# sensor-6.net
KiCad netlist of a schematic drawn in Altium Designer
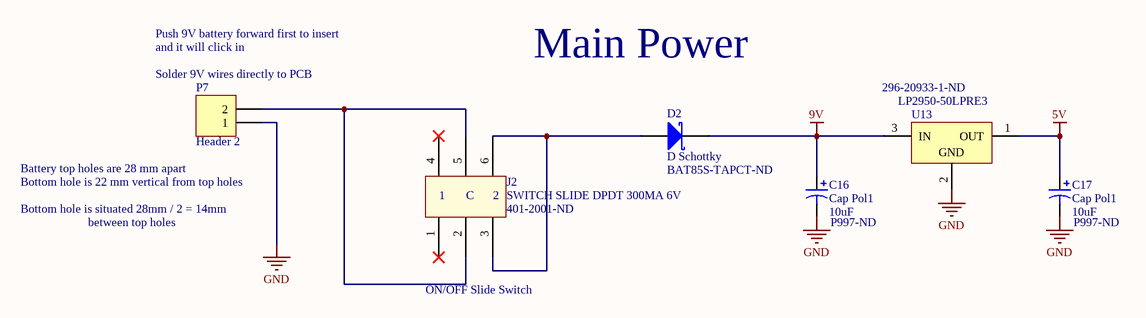
[diagram p0: sensor-6.SchDoc]

(export (version "E")
  (design (tool "Eeschema 10.0.6"))
  (components
    (comp (ref "C16")
      (value "Cap Pol1")
      (footprint "ECE-A1HKS100")
      (description "Polarized Capacitor (Radial)")
      (fields
        (field (name "ALTIUM_VALUE") "10uF")
        (field (name "SUPPLIER PART NUMBER 1") "P997-ND")
        (field (name "MANUFACTURER") "Panasonic")
        (field (name "MANUFACTURER PART NUMBER") "ECE-A1HKS100")
        (field (name "PUBLISHER") "Altium Limited")
      )
      (libsource (lib "Miscellaneous Devices") (part "Cap Pol1"))
    )
    (comp (ref "C17")
      (value "Cap Pol1")
      (footprint "ECE-A1HKS100")
      (description "Polarized Capacitor (Radial)")
      (fields
        (field (name "ALTIUM_VALUE") "10uF")
        (field (name "SUPPLIER PART NUMBER 1") "P997-ND")
        (field (name "MANUFACTURER") "Panasonic")
        (field (name "MANUFACTURER PART NUMBER") "ECE-A1HKS100")
        (field (name "PUBLISHER") "Altium Limited")
      )
      (libsource (lib "Miscellaneous Devices") (part "Cap Pol1"))
    )
    (comp (ref "D2")
      (value "D Schottky")
      (footprint "BAT85S-TAP")
      (description "Schottky Diode")
      (fields
        (field (name "SUPPLIER PART NUMBER 1") "BAT85S-TAPCT-ND")
        (field (name "MANUFACTURER") "Vishay")
        (field (name "MANUFACTURER PART NUMBER") "BAT85S-TAP")
        (field (name "PUBLISHER") "Altium Limited")
      )
      (libsource (lib "Miscellaneous Devices") (part "D Schottky"))
    )
    (comp (ref "J2")
      (value "SWITCH SLIDE DPDT 300MA 6V")
      (footprint "JS202011CQN")
      (fields
        (field (name "SUPPLIER PART NUMBER 1") "401-2001-ND")
        (field (name "MANUFACTURER") "ITT C&K")
        (field (name "MANUFACTURER PART NUMBER") "JS202011CQN")
      )
      (libsource (lib "CK") (part "JS202011CQN"))
    )
    (comp (ref "P7")
      (value "Header 2")
      (footprint "HDR1X2")
      (description "Header, 2-Pin")
      (fields (field (name "PUBLISHER") "Altium Limited"))
      (libsource (lib "Miscellaneous Connectors") (part "Header 2"))
    )
    (comp (ref "U13")
      (value "LP2950-50LPRE3")
      (footprint "LP0003A")
      (fields
        (field (name "MANUFACTURER") "Texas Instruments")
        (field (name "SUPPLIER PART NUMBER 1") "296-20933-1-ND")
      )
      (libsource (lib "Altium Content Vault") (part "TI-LP2590-LP3"))
    )
  )
  (nets
    (net (code "1") (name "5V") (class "Default")
      (node (ref "C17") (pin "1") (pinfunction "1_1") (pintype "passive"))
      (node (ref "U13") (pin "1") (pinfunction "OUT_1") (pintype "power_in"))
    )
    (net (code "2") (name "9V") (class "Default")
      (node (ref "C16") (pin "1") (pinfunction "1_1") (pintype "passive"))
      (node (ref "D2") (pin "2") (pinfunction "K_2") (pintype "passive"))
      (node (ref "U13") (pin "3") (pinfunction "IN_3") (pintype "power_in"))
    )
    (net (code "3") (name "GND") (class "Default")
      (node (ref "C16") (pin "2") (pinfunction "2_2") (pintype "passive"))
      (node (ref "C17") (pin "2") (pinfunction "2_2") (pintype "passive"))
      (node (ref "P7") (pin "1") (pinfunction "1_1") (pintype "passive"))
      (node (ref "U13") (pin "2") (pinfunction "GND_2") (pintype "power_in"))
    )
    (net (code "4") (name "Net-(D2-A)") (class "Default")
      (node (ref "D2") (pin "1") (pinfunction "A_1") (pintype "passive"))
      (node (ref "J2") (pin "3") (pinfunction "3_3") (pintype "passive"))
      (node (ref "J2") (pin "6") (pinfunction "6_6") (pintype "passive"))
    )
    (net (code "5") (name "Net-(J2-Pad2)") (class "Default")
      (node (ref "J2") (pin "2") (pinfunction "2_2") (pintype "passive"))
      (node (ref "J2") (pin "5") (pinfunction "5_5") (pintype "passive"))
      (node (ref "P7") (pin "2") (pinfunction "2_2") (pintype "passive"))
    )
    (net (code "6") (name "unconnected-(J2-Pad1)") (class "Default")
      (node (ref "J2") (pin "1") (pinfunction "1_1") (pintype "passive+no_connect"))
    )
    (net (code "7") (name "unconnected-(J2-Pad4)") (class "Default")
      (node (ref "J2") (pin "4") (pinfunction "4_4") (pintype "passive+no_connect"))
    )
  )
)
